# Filter_Capacitors_-_External_SIM.net
KiCad netlist of a schematic drawn in Altium Designer
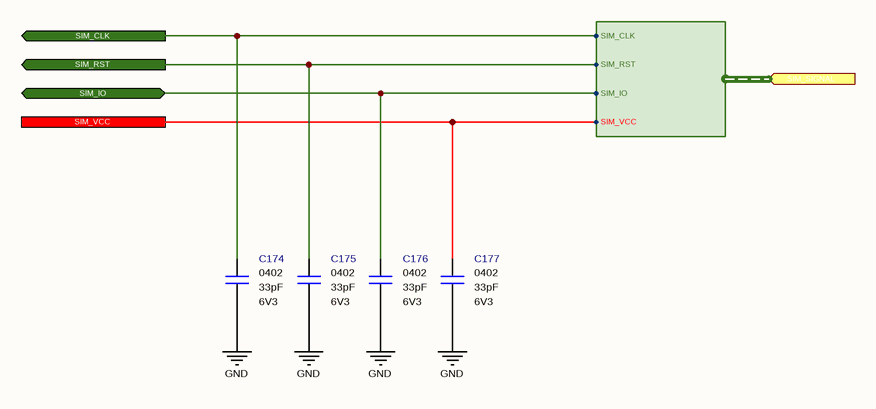
[diagram p0: Filter Capacitors - External SIM.SchDoc]

(export (version "E")
  (design (tool "Eeschema 10.0.6"))
  (components
    (comp (ref "C174")
      (value "33pF")
      (footprint "CAPACITOR_0402")
      (description "Capacitor - 33pF [0402] (Ceramic)")
      (fields
        (field (name "TOLERANCE") "10%")
        (field (name "CASE") "0402")
        (field (name "VOLTAGE") "6V3")
        (field (name "MANUFACTURER PART NUMBER") "C0402C330J9RACAUTO")
      )
      (libsource (lib "Ovoo_Library") (part "Capacitor - 33pF [0402-6V3]"))
    )
    (comp (ref "C175")
      (value "33pF")
      (footprint "CAPACITOR_0402")
      (description "Capacitor - 33pF [0402] (Ceramic)")
      (fields
        (field (name "TOLERANCE") "10%")
        (field (name "CASE") "0402")
        (field (name "VOLTAGE") "6V3")
        (field (name "MANUFACTURER PART NUMBER") "C0402C330J9RACAUTO")
      )
      (libsource (lib "Ovoo_Library") (part "Capacitor - 33pF [0402-6V3]"))
    )
    (comp (ref "C176")
      (value "33pF")
      (footprint "CAPACITOR_0402")
      (description "Capacitor - 33pF [0402] (Ceramic)")
      (fields
        (field (name "TOLERANCE") "10%")
        (field (name "CASE") "0402")
        (field (name "VOLTAGE") "6V3")
        (field (name "MANUFACTURER PART NUMBER") "C0402C330J9RACAUTO")
      )
      (libsource (lib "Ovoo_Library") (part "Capacitor - 33pF [0402-6V3]"))
    )
    (comp (ref "C177")
      (value "33pF")
      (footprint "CAPACITOR_0402")
      (description "Capacitor - 33pF [0402] (Ceramic)")
      (fields
        (field (name "TOLERANCE") "10%")
        (field (name "CASE") "0402")
        (field (name "VOLTAGE") "6V3")
        (field (name "MANUFACTURER PART NUMBER") "C0402C330J9RACAUTO")
      )
      (libsource (lib "Ovoo_Library") (part "Capacitor - 33pF [0402-6V3]"))
    )
  )
  (nets
    (net (code "2") (name "/SIM_CLK") (class "Default")
      (node (ref "C174") (pin "2") (pinfunction "2_2") (pintype "passive"))
    )
    (net (code "3") (name "/SIM_IO") (class "Default")
      (node (ref "C176") (pin "2") (pinfunction "2_2") (pintype "passive"))
    )
    (net (code "4") (name "/SIM_RST") (class "Default")
      (node (ref "C175") (pin "2") (pinfunction "2_2") (pintype "passive"))
    )
    (net (code "5") (name "/SIM_VCC") (class "Default")
      (node (ref "C177") (pin "2") (pinfunction "2_2") (pintype "passive"))
    )
    (net (code "7") (name "GND") (class "Default")
      (node (ref "C174") (pin "1") (pinfunction "1_1") (pintype "passive"))
      (node (ref "C175") (pin "1") (pinfunction "1_1") (pintype "passive"))
      (node (ref "C176") (pin "1") (pinfunction "1_1") (pintype "passive"))
      (node (ref "C177") (pin "1") (pinfunction "1_1") (pintype "passive"))
    )
  )
)
